# CLKB_analog_phase_detector.net
KiCad netlist of a schematic drawn in Altium Designer
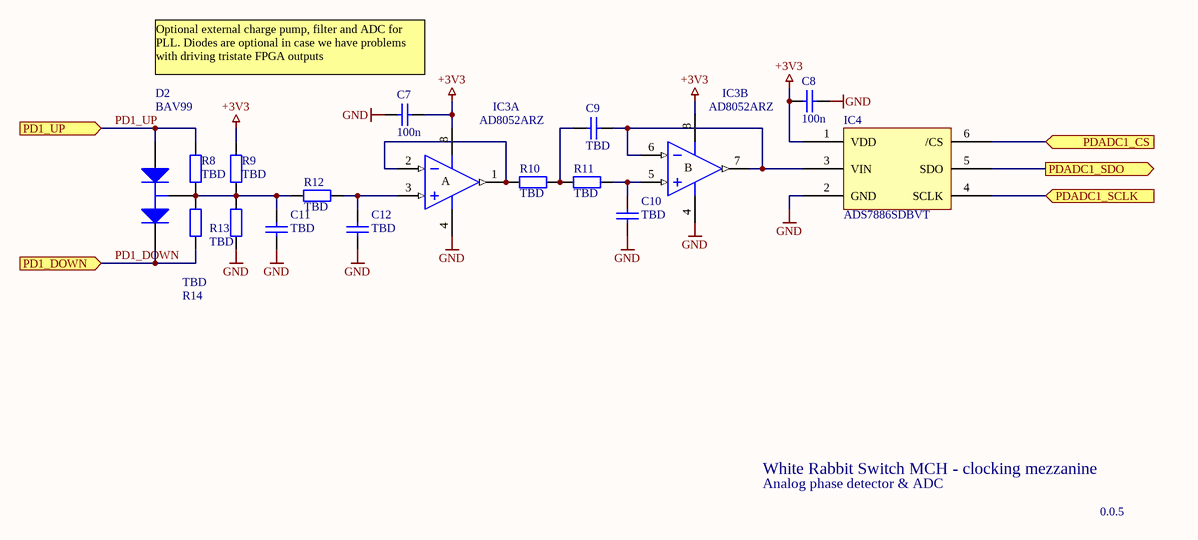
[diagram p0: CLKB_analog_phase_detector.SchDoc]

(export (version "E")
  (design (tool "Eeschema 10.0.6"))
  (components
    (comp (ref "C7")
      (value "100n")
      (footprint "CAPC1608X87N")
      (description "Capacitor")
      (fields (field (name "PUBLISHER") "Altium Limited"))
      (libsource (lib "Miscellaneous Devices") (part "Cap"))
    )
    (comp (ref "C8")
      (value "100n")
      (footprint "CC1608-0603")
      (description "Capacitor")
      (fields (field (name "PUBLISHER") "Altium Limited"))
      (libsource (lib "Miscellaneous Devices") (part "Cap"))
    )
    (comp (ref "C9")
      (value "TBD")
      (footprint "CAPC1608X87N")
      (description "Capacitor")
      (fields (field (name "PUBLISHER") "Altium Limited"))
      (libsource (lib "Miscellaneous Devices") (part "Cap"))
    )
    (comp (ref "C10")
      (value "TBD")
      (footprint "CAPC1608X87N")
      (description "Capacitor")
      (fields (field (name "PUBLISHER") "Altium Limited"))
      (libsource (lib "Miscellaneous Devices") (part "Cap"))
    )
    (comp (ref "C11")
      (value "TBD")
      (footprint "CAPC1608X87N")
      (description "Capacitor")
      (fields (field (name "PUBLISHER") "Altium Limited"))
      (libsource (lib "Miscellaneous Devices") (part "Cap"))
    )
    (comp (ref "C12")
      (value "TBD")
      (footprint "CAPC1608X87N")
      (description "Capacitor")
      (fields (field (name "PUBLISHER") "Altium Limited"))
      (libsource (lib "Miscellaneous Devices") (part "Cap"))
    )
    (comp (ref "D2")
      (value "BAV99")
      (footprint "SOT-23")
      (description "Silicon Switching Diode Array for High-Speed Switching")
      (fields (field (name "Comment") "BAV99*") (field (name "PUBLISHER") "Altium Limited"))
      (libsource (lib "Infineon Discrete Diode") (part "BAV99"))
    )
    (comp (ref "IC3")
      (value "AD8052ARZ")
      (footprint "SOIC127P600-8AL")
      (description "Low Cost, High-Speed Rail-to-Rail Amplifier")
      (fields (field (name "Comment") "AD8052*") (field (name "PUBLISHER") "Altium Limited"))
      (libsource (lib "wr_switch") (part "AD8052"))
    )
    (comp (ref "IC4")
      (value "ADS7886SDBVT")
      (footprint "SOT23A-6L")
      (description "TI 1 MSPS serial ADC")
      (fields (field (name "Comment") "ADS7886*"))
      (libsource (lib "wr_switch") (part "ADS7886"))
    )
    (comp (ref "R8")
      (value "TBD")
      (footprint "RESC1608X55N")
      (description "Resistor")
      (fields (field (name "PUBLISHER") "Altium Limited"))
      (libsource (lib "") (part "Res2_1"))
    )
    (comp (ref "R9")
      (value "TBD")
      (footprint "RESC1608X55N")
      (description "Resistor")
      (fields (field (name "PUBLISHER") "Altium Limited"))
      (libsource (lib "") (part "Res2_1"))
    )
    (comp (ref "R10")
      (value "TBD")
      (footprint "RESC1608X55N")
      (description "Resistor")
      (fields (field (name "PUBLISHER") "Altium Limited"))
      (libsource (lib "Miscellaneous Devices") (part "Res2"))
    )
    (comp (ref "R11")
      (value "TBD")
      (footprint "RESC1608X55N")
      (description "Resistor")
      (fields (field (name "PUBLISHER") "Altium Limited"))
      (libsource (lib "Miscellaneous Devices") (part "Res2"))
    )
    (comp (ref "R12")
      (value "TBD")
      (footprint "RESC1608X55N")
      (description "Resistor")
      (fields (field (name "PUBLISHER") "Altium Limited"))
      (libsource (lib "Miscellaneous Devices") (part "Res2"))
    )
    (comp (ref "R13")
      (value "TBD")
      (footprint "RESC1608X55N")
      (description "Resistor")
      (fields (field (name "PUBLISHER") "Altium Limited"))
      (libsource (lib "") (part "Res2_1"))
    )
    (comp (ref "R14")
      (value "TBD")
      (footprint "RESC1608X55N")
      (description "Resistor")
      (fields (field (name "PUBLISHER") "Altium Limited"))
      (libsource (lib "") (part "Res2_1"))
    )
  )
  (nets
    (net (code "1") (name "+3V3") (class "Default")
      (node (ref "C7") (pin "1") (pinfunction "1_1") (pintype "passive"))
      (node (ref "C8") (pin "1") (pinfunction "1_1") (pintype "passive"))
      (node (ref "IC3") (pin "8") (pinfunction "V+_8") (pintype "power_in"))
      (node (ref "IC4") (pin "1") (pinfunction "VDD_1") (pintype "passive"))
      (node (ref "R9") (pin "2") (pinfunction "2_2") (pintype "passive"))
    )
    (net (code "2") (name "/PD1_DOWN") (class "Default")
      (node (ref "D2") (pin "2") (pinfunction "K_2") (pintype "passive"))
      (node (ref "R14") (pin "1") (pinfunction "1_1") (pintype "passive"))
    )
    (net (code "3") (name "/PD1_UP") (class "Default")
      (node (ref "D2") (pin "1") (pinfunction "A_1") (pintype "passive"))
      (node (ref "R8") (pin "2") (pinfunction "2_2") (pintype "passive"))
    )
    (net (code "4") (name "/PDADC1_CS") (class "Default")
      (node (ref "IC4") (pin "6") (pinfunction "/CS_6") (pintype "passive"))
    )
    (net (code "5") (name "/PDADC1_SCLK") (class "Default")
      (node (ref "IC4") (pin "4") (pinfunction "SCLK_4") (pintype "passive"))
    )
    (net (code "6") (name "/PDADC1_SDO") (class "Default")
      (node (ref "IC4") (pin "5") (pinfunction "SDO_5") (pintype "passive"))
    )
    (net (code "7") (name "GND") (class "Default")
      (node (ref "C10") (pin "1") (pinfunction "1_1") (pintype "passive"))
      (node (ref "C11") (pin "1") (pinfunction "1_1") (pintype "passive"))
      (node (ref "C12") (pin "1") (pinfunction "1_1") (pintype "passive"))
      (node (ref "C7") (pin "2") (pinfunction "2_2") (pintype "passive"))
      (node (ref "C8") (pin "2") (pinfunction "2_2") (pintype "passive"))
      (node (ref "IC3") (pin "4") (pinfunction "V-_4") (pintype "power_in"))
      (node (ref "IC4") (pin "2") (pinfunction "GND_2") (pintype "passive"))
      (node (ref "R13") (pin "1") (pinfunction "1_1") (pintype "passive"))
    )
    (net (code "8") (name "Net-(C9-Pad2)") (class "Default")
      (node (ref "C9") (pin "2") (pinfunction "2_2") (pintype "passive"))
      (node (ref "R10") (pin "2") (pinfunction "2_2") (pintype "passive"))
      (node (ref "R11") (pin "1") (pinfunction "1_1") (pintype "passive"))
    )
    (net (code "9") (name "Net-(D2-C)") (class "Default")
      (node (ref "C11") (pin "2") (pinfunction "2_2") (pintype "passive"))
      (node (ref "D2") (pin "3") (pinfunction "C_3") (pintype "passive"))
      (node (ref "R12") (pin "1") (pinfunction "1_1") (pintype "passive"))
      (node (ref "R13") (pin "2") (pinfunction "2_2") (pintype "passive"))
      (node (ref "R14") (pin "2") (pinfunction "2_2") (pintype "passive"))
      (node (ref "R8") (pin "1") (pinfunction "1_1") (pintype "passive"))
      (node (ref "R9") (pin "1") (pinfunction "1_1") (pintype "passive"))
    )
    (net (code "10") (name "Net-(IC3A-IN+)") (class "Default")
      (node (ref "C12") (pin "2") (pinfunction "2_2") (pintype "passive"))
      (node (ref "IC3") (pin "3") (pinfunction "IN+_3") (pintype "input"))
      (node (ref "R12") (pin "2") (pinfunction "2_2") (pintype "passive"))
    )
    (net (code "11") (name "Net-(IC3A-IN-)") (class "Default")
      (node (ref "IC3") (pin "1") (pinfunction "OUT_1") (pintype "output"))
      (node (ref "IC3") (pin "2") (pinfunction "IN-_2") (pintype "input"))
      (node (ref "R10") (pin "1") (pinfunction "1_1") (pintype "passive"))
    )
    (net (code "12") (name "Net-(IC3B-IN+)") (class "Default")
      (node (ref "C10") (pin "2") (pinfunction "2_2") (pintype "passive"))
      (node (ref "IC3") (pin "5") (pinfunction "IN+_5") (pintype "input"))
      (node (ref "R11") (pin "2") (pinfunction "2_2") (pintype "passive"))
    )
    (net (code "13") (name "Net-(IC3B-IN-)") (class "Default")
      (node (ref "C9") (pin "1") (pinfunction "1_1") (pintype "passive"))
      (node (ref "IC3") (pin "6") (pinfunction "IN-_6") (pintype "input"))
      (node (ref "IC3") (pin "7") (pinfunction "OUT_7") (pintype "output"))
      (node (ref "IC4") (pin "3") (pinfunction "VIN_3") (pintype "passive"))
    )
  )
)
